# 05_-_RF_READER.net
KiCad netlist of a schematic drawn in Altium Designer
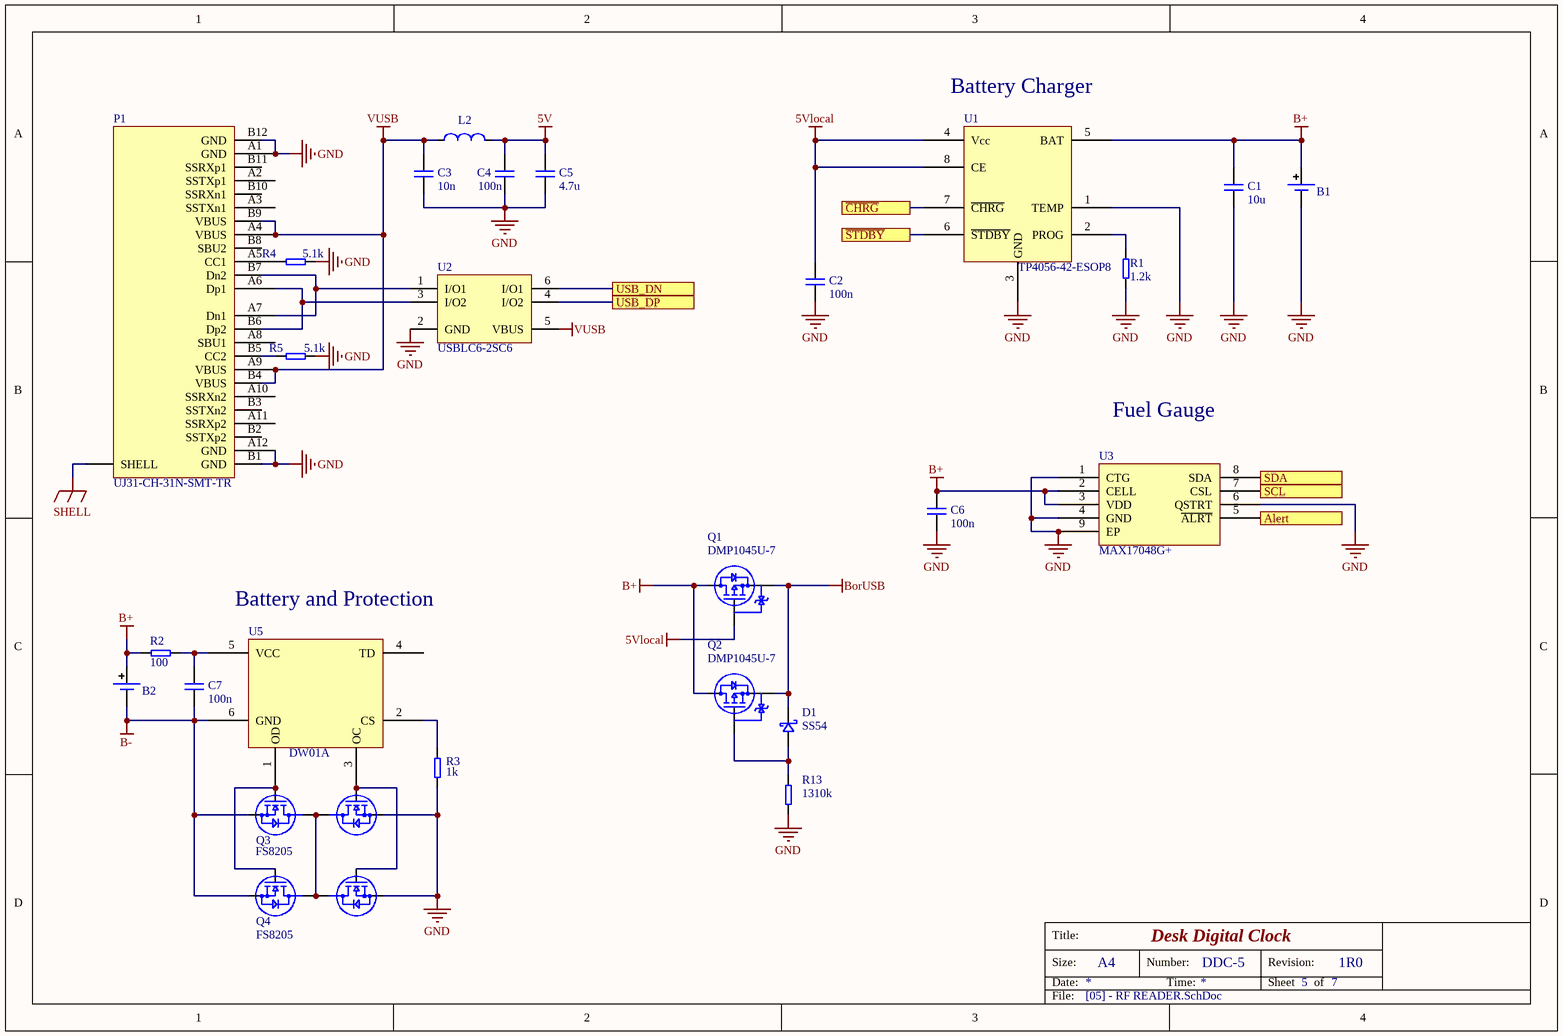
[diagram p0: [05] - RF READER.SchDoc]

(export (version "E")
  (design (tool "Eeschema 10.0.6"))
  (components
    (comp (ref "B1") (value "~") (description "BATTERY") (libsource (lib "1") (part "Bat")))
    (comp (ref "B2") (value "~") (description "BATTERY") (libsource (lib "1") (part "Bat")))
    (comp (ref "C1")
      (value "10u")
      (footprint "C0603")
      (description "CAPACITOR")
      (libsource (lib "1") (part "Cap"))
    )
    (comp (ref "C2")
      (value "100n")
      (footprint "C0603")
      (description "CAPACITOR")
      (libsource (lib "1") (part "Cap"))
    )
    (comp (ref "C3")
      (value "10n")
      (footprint "C0603")
      (description "CAPACITOR")
      (libsource (lib "1") (part "Cap"))
    )
    (comp (ref "C4")
      (value "100n")
      (footprint "C0603")
      (description "CAPACITOR")
      (libsource (lib "1") (part "Cap"))
    )
    (comp (ref "C5")
      (value "4.7u")
      (footprint "C0603")
      (description "CAPACITOR")
      (libsource (lib "1") (part "Cap"))
    )
    (comp (ref "C6")
      (value "100n")
      (footprint "C0603")
      (description "CAPACITOR")
      (libsource (lib "1") (part "Cap"))
    )
    (comp (ref "C7")
      (value "100n")
      (footprint "C0603")
      (description "CAPACITOR")
      (libsource (lib "1") (part "Cap"))
    )
    (comp (ref "D1")
      (value "~")
      (footprint "DIOM6959X26N-SS54")
      (description "Diode Shottky")
      (fields (field (name "P/N") "SS54"))
      (libsource (lib "1") (part "Diode_Shottky"))
    )
    (comp (ref "L2")
      (value "~")
      (footprint "C0805")
      (description "Ferrite Bead")
      (libsource (lib "1") (part "Ind"))
    )
    (comp (ref "P1")
      (value "UJ31-CH-31N-SMT-TR")
      (footprint "UJ31-CH-31N-SMT-TR")
      (description "CONN RCPT USB3.1 TYPEC 24POS R/A")
      (fields (field (name "MANUFACTURER") "CUI Devices"))
      (libsource (lib "1") (part "UJ31-CH-31N-SMT-TR"))
    )
    (comp (ref "Q1")
      (value "DMP1045U-7")
      (footprint "SOT23127P600-8N")
      (description "P-CHANNEL ENHANCEMENT MODE MOSFET")
      (fields (field (name "MANUFACTURER") "Diodes Incorporated"))
      (libsource (lib "1") (part "DMP1045U-7"))
    )
    (comp (ref "Q2")
      (value "DMP1045U-7")
      (footprint "SOT23127P600-8N")
      (description "P-CHANNEL ENHANCEMENT MODE MOSFET")
      (fields (field (name "MANUFACTURER") "Diodes Incorporated"))
      (libsource (lib "1") (part "DMP1045U-7"))
    )
    (comp (ref "Q3")
      (value "FS8205")
      (footprint "SOT23-6-MT3420C")
      (description "Dual n-Channel Enhancement Mode power MOSFET")
      (fields (field (name "MANUFACTURER") "Fortune"))
      (libsource (lib "1") (part "FS8205"))
    )
    (comp (ref "Q4")
      (value "FS8205")
      (footprint "SOT23-6-MT3420C")
      (description "Dual n-Channel Enhancement Mode power MOSFET")
      (fields (field (name "MANUFACTURER") "Fortune"))
      (libsource (lib "1") (part "FS8205"))
    )
    (comp (ref "R1")
      (value "1.2k")
      (footprint "R0603")
      (description "RESISTOR")
      (libsource (lib "1") (part "Res"))
    )
    (comp (ref "R2")
      (value "100")
      (footprint "R0603")
      (description "RESISTOR")
      (libsource (lib "1") (part "Res"))
    )
    (comp (ref "R3")
      (value "1k")
      (footprint "R0603")
      (description "RESISTOR")
      (libsource (lib "1") (part "Res"))
    )
    (comp (ref "R4")
      (value "5.1k")
      (footprint "R0603")
      (description "RESISTOR")
      (libsource (lib "1") (part "Res"))
    )
    (comp (ref "R5")
      (value "5.1k")
      (footprint "R0603")
      (description "RESISTOR")
      (libsource (lib "1") (part "Res"))
    )
    (comp (ref "R13")
      (value "1310k")
      (footprint "R0603")
      (description "RESISTOR")
      (libsource (lib "1") (part "Res"))
    )
    (comp (ref "U1")
      (value "TP4056-42-ESOP8")
      (footprint "TP4056-SOIC8-TP")
      (description "1A Standalone Linear Li-lon Battery Charger with Thermal\r\nRegulation in SOP-8")
      (fields (field (name "MANUFACTURER") "TopPower"))
      (libsource (lib "1") (part "TP4056-42-ESOP8"))
    )
    (comp (ref "U2")
      (value "USBLC6-2SC6")
      (footprint "SOT23-6L-USBLC6-2SC6")
      (description "TVS DIODE 5.25V 17V SOT23-6")
      (fields (field (name "MANUFACTURER") "STMicroelectronics"))
      (libsource (lib "1") (part "USBLC6-2SC6"))
    )
    (comp (ref "U3")
      (value "MAX17048G+")
      (footprint "8 TDFN-EP-MAX17048G+")
      (description "Micropower 1 Cell Li+ ModelFuel Gauge")
      (fields (field (name "MANUFACTURER") "Maxim Integrated"))
      (libsource (lib "1") (part "MAX17048G+"))
    )
    (comp (ref "U5")
      (value "DW01A")
      (footprint "SOT23-6-MT3420C")
      (description "2A 2.3-6V Input 1.5MHz Synchronous Step-Down Converter")
      (fields (field (name "MANUFACTURER") "HMsemi"))
      (libsource (lib "1") (part "DW01A"))
    )
  )
  (nets
    (net (code "1") (name "/Alert") (class "Default")
      (node (ref "U3") (pin "5") (pinfunction "~{ALRT}_5") (pintype "passive"))
    )
    (net (code "2") (name "/SCL") (class "Default")
      (node (ref "U3") (pin "7") (pinfunction "CSL_7") (pintype "passive"))
    )
    (net (code "3") (name "/SDA") (class "Default")
      (node (ref "U3") (pin "8") (pinfunction "SDA_8") (pintype "passive"))
    )
    (net (code "4") (name "/USB_DN") (class "Default")
      (node (ref "U2") (pin "6") (pinfunction "I/O1_6") (pintype "passive"))
    )
    (net (code "5") (name "/USB_DP") (class "Default")
      (node (ref "U2") (pin "4") (pinfunction "I/O2_4") (pintype "passive"))
    )
    (net (code "6") (name "/~{CHRG}") (class "Default")
      (node (ref "U1") (pin "7") (pinfunction "~{CHRG}_7") (pintype "passive"))
    )
    (net (code "7") (name "/~{STDBY}") (class "Default")
      (node (ref "U1") (pin "6") (pinfunction "~{STDBY}_6") (pintype "passive"))
    )
    (net (code "8") (name "5V") (class "Default")
      (node (ref "C4") (pin "2") (pinfunction "2_2") (pintype "passive"))
      (node (ref "C5") (pin "2") (pinfunction "2_2") (pintype "passive"))
      (node (ref "L2") (pin "2") (pinfunction "2_2") (pintype "passive"))
    )
    (net (code "9") (name "5Vlocal") (class "Default")
      (node (ref "C2") (pin "2") (pinfunction "2_2") (pintype "passive"))
      (node (ref "Q1") (pin "G") (pinfunction "G_G") (pintype "passive"))
      (node (ref "U1") (pin "4") (pinfunction "Vcc_4") (pintype "passive"))
      (node (ref "U1") (pin "8") (pinfunction "CE_8") (pintype "passive"))
    )
    (net (code "10") (name "B+") (class "Default")
      (node (ref "B1") (pin "2") (pinfunction "2_2") (pintype "passive"))
      (node (ref "B2") (pin "2") (pinfunction "2_2") (pintype "passive"))
      (node (ref "C1") (pin "2") (pinfunction "2_2") (pintype "passive"))
      (node (ref "C6") (pin "2") (pinfunction "2_2") (pintype "passive"))
      (node (ref "Q1") (pin "D") (pinfunction "D_D") (pintype "passive"))
      (node (ref "Q2") (pin "D") (pinfunction "D_D") (pintype "passive"))
      (node (ref "R2") (pin "2") (pinfunction "2_2") (pintype "passive"))
      (node (ref "U1") (pin "5") (pinfunction "BAT_5") (pintype "passive"))
      (node (ref "U3") (pin "2") (pinfunction "CELL_2") (pintype "passive"))
      (node (ref "U3") (pin "3") (pinfunction "VDD_3") (pintype "passive"))
    )
    (net (code "11") (name "B-") (class "Default")
      (node (ref "B2") (pin "1") (pinfunction "1_1") (pintype "passive"))
      (node (ref "C7") (pin "1") (pinfunction "1_1") (pintype "passive"))
      (node (ref "Q3") (pin "1") (pinfunction "S1_1") (pintype "passive"))
      (node (ref "Q4") (pin "1") (pinfunction "S1_1") (pintype "passive"))
      (node (ref "U5") (pin "6") (pinfunction "GND_6") (pintype "passive"))
    )
    (net (code "12") (name "BorUSB") (class "Default")
      (node (ref "D1") (pin "1") (pinfunction "1_1") (pintype "passive"))
      (node (ref "Q1") (pin "S") (pinfunction "S_S") (pintype "passive"))
      (node (ref "Q2") (pin "S") (pinfunction "S_S") (pintype "passive"))
    )
    (net (code "13") (name "GND") (class "Default")
      (node (ref "B1") (pin "1") (pinfunction "1_1") (pintype "passive"))
      (node (ref "C1") (pin "1") (pinfunction "1_1") (pintype "passive"))
      (node (ref "C2") (pin "1") (pinfunction "1_1") (pintype "passive"))
      (node (ref "C3") (pin "1") (pinfunction "1_1") (pintype "passive"))
      (node (ref "C4") (pin "1") (pinfunction "1_1") (pintype "passive"))
      (node (ref "C5") (pin "1") (pinfunction "1_1") (pintype "passive"))
      (node (ref "C6") (pin "1") (pinfunction "1_1") (pintype "passive"))
      (node (ref "P1") (pin "A1") (pinfunction "GND_A1") (pintype "passive"))
      (node (ref "P1") (pin "A12") (pinfunction "GND_A12") (pintype "passive"))
      (node (ref "P1") (pin "B1") (pinfunction "GND_B1") (pintype "passive"))
      (node (ref "P1") (pin "B12") (pinfunction "GND_B12") (pintype "passive"))
      (node (ref "Q3") (pin "3") (pinfunction "S2_3") (pintype "passive"))
      (node (ref "Q4") (pin "3") (pinfunction "S2_3") (pintype "passive"))
      (node (ref "R1") (pin "1") (pinfunction "1_1") (pintype "passive"))
      (node (ref "R13") (pin "1") (pinfunction "1_1") (pintype "passive"))
      (node (ref "R3") (pin "1") (pinfunction "1_1") (pintype "passive"))
      (node (ref "R4") (pin "1") (pinfunction "1_1") (pintype "passive"))
      (node (ref "R5") (pin "1") (pinfunction "1_1") (pintype "passive"))
      (node (ref "U1") (pin "1") (pinfunction "TEMP_1") (pintype "passive"))
      (node (ref "U1") (pin "3") (pinfunction "GND_3") (pintype "passive"))
      (node (ref "U2") (pin "2") (pinfunction "GND_2") (pintype "passive"))
      (node (ref "U3") (pin "1") (pinfunction "CTG_1") (pintype "passive"))
      (node (ref "U3") (pin "4") (pinfunction "GND_4") (pintype "passive"))
      (node (ref "U3") (pin "6") (pinfunction "QSTRT_6") (pintype "passive"))
      (node (ref "U3") (pin "9") (pinfunction "EP_9") (pintype "passive"))
    )
    (net (code "14") (name "Net-(D1-Pad2)") (class "Default")
      (node (ref "D1") (pin "2") (pinfunction "2_2") (pintype "passive"))
      (node (ref "Q2") (pin "G") (pinfunction "G_G") (pintype "passive"))
      (node (ref "R13") (pin "2") (pinfunction "2_2") (pintype "passive"))
    )
    (net (code "15") (name "Net-(P1-CC1)") (class "Default")
      (node (ref "P1") (pin "A5") (pinfunction "CC1_A5") (pintype "passive"))
      (node (ref "R4") (pin "2") (pinfunction "2_2") (pintype "passive"))
    )
    (net (code "16") (name "Net-(P1-CC2)") (class "Default")
      (node (ref "P1") (pin "B5") (pinfunction "CC2_B5") (pintype "passive"))
      (node (ref "R5") (pin "2") (pinfunction "2_2") (pintype "passive"))
    )
    (net (code "17") (name "Net-(P1-Dn1)") (class "Default")
      (node (ref "P1") (pin "A7") (pinfunction "Dn1_A7") (pintype "passive"))
      (node (ref "P1") (pin "B7") (pinfunction "Dn2_B7") (pintype "passive"))
      (node (ref "U2") (pin "1") (pinfunction "I/O1_1") (pintype "passive"))
    )
    (net (code "18") (name "Net-(P1-Dp1)") (class "Default")
      (node (ref "P1") (pin "A6") (pinfunction "Dp1_A6") (pintype "passive"))
      (node (ref "P1") (pin "B6") (pinfunction "Dp2_B6") (pintype "passive"))
      (node (ref "U2") (pin "3") (pinfunction "I/O2_3") (pintype "passive"))
    )
    (net (code "19") (name "Net-(Q3-D12-Pad2)") (class "Default")
      (node (ref "Q3") (pin "2") (pinfunction "D12_2") (pintype "passive"))
      (node (ref "Q3") (pin "5") (pinfunction "D12_5") (pintype "passive"))
      (node (ref "Q4") (pin "2") (pinfunction "D12_2") (pintype "passive"))
      (node (ref "Q4") (pin "5") (pinfunction "D12_5") (pintype "passive"))
    )
    (net (code "20") (name "Net-(Q3-G1)") (class "Default")
      (node (ref "Q3") (pin "6") (pinfunction "G1_6") (pintype "passive"))
      (node (ref "Q4") (pin "6") (pinfunction "G1_6") (pintype "passive"))
      (node (ref "U5") (pin "1") (pinfunction "OD_1") (pintype "passive"))
    )
    (net (code "21") (name "Net-(Q3-G2)") (class "Default")
      (node (ref "Q3") (pin "4") (pinfunction "G2_4") (pintype "passive"))
      (node (ref "Q4") (pin "4") (pinfunction "G2_4") (pintype "passive"))
      (node (ref "U5") (pin "3") (pinfunction "OC_3") (pintype "passive"))
    )
    (net (code "22") (name "Net-(U1-PROG)") (class "Default")
      (node (ref "R1") (pin "2") (pinfunction "2_2") (pintype "passive"))
      (node (ref "U1") (pin "2") (pinfunction "PROG_2") (pintype "passive"))
    )
    (net (code "23") (name "Net-(U5-CS)") (class "Default")
      (node (ref "R3") (pin "2") (pinfunction "2_2") (pintype "passive"))
      (node (ref "U5") (pin "2") (pinfunction "CS_2") (pintype "passive"))
    )
    (net (code "24") (name "Net-(U5-VCC)") (class "Default")
      (node (ref "C7") (pin "2") (pinfunction "2_2") (pintype "passive"))
      (node (ref "R2") (pin "1") (pinfunction "1_1") (pintype "passive"))
      (node (ref "U5") (pin "5") (pinfunction "VCC_5") (pintype "passive"))
    )
    (net (code "25") (name "SHELL") (class "Default")
      (node (ref "P1") (pin "0") (pinfunction "SHELL_0") (pintype "passive"))
    )
    (net (code "26") (name "VUSB") (class "Default")
      (node (ref "C3") (pin "2") (pinfunction "2_2") (pintype "passive"))
      (node (ref "L2") (pin "1") (pinfunction "1_1") (pintype "passive"))
      (node (ref "P1") (pin "A4") (pinfunction "VBUS_A4") (pintype "passive"))
      (node (ref "P1") (pin "A9") (pinfunction "VBUS_A9") (pintype "passive"))
      (node (ref "P1") (pin "B4") (pinfunction "VBUS_B4") (pintype "passive"))
      (node (ref "P1") (pin "B9") (pinfunction "VBUS_B9") (pintype "passive"))
      (node (ref "U2") (pin "5") (pinfunction "VBUS_5") (pintype "passive"))
    )
    (net (code "27") (name "unconnected-(P1-SBU1-PadA8)") (class "Default")
      (node (ref "P1") (pin "A8") (pinfunction "SBU1_A8") (pintype "passive"))
    )
    (net (code "28") (name "unconnected-(P1-SBU2-PadB8)") (class "Default")
      (node (ref "P1") (pin "B8") (pinfunction "SBU2_B8") (pintype "passive"))
    )
    (net (code "29") (name "unconnected-(P1-SSRXn1-PadB10)") (class "Default")
      (node (ref "P1") (pin "B10") (pinfunction "SSRXn1_B10") (pintype "passive"))
    )
    (net (code "30") (name "unconnected-(P1-SSRXn2-PadA10)") (class "Default")
      (node (ref "P1") (pin "A10") (pinfunction "SSRXn2_A10") (pintype "passive"))
    )
    (net (code "31") (name "unconnected-(P1-SSRXp1-PadB11)") (class "Default")
      (node (ref "P1") (pin "B11") (pinfunction "SSRXp1_B11") (pintype "passive"))
    )
    (net (code "32") (name "unconnected-(P1-SSRXp2-PadA11)") (class "Default")
      (node (ref "P1") (pin "A11") (pinfunction "SSRXp2_A11") (pintype "passive"))
    )
    (net (code "33") (name "unconnected-(P1-SSTXn1-PadA3)") (class "Default")
      (node (ref "P1") (pin "A3") (pinfunction "SSTXn1_A3") (pintype "passive"))
    )
    (net (code "34") (name "unconnected-(P1-SSTXn2-PadB3)") (class "Default")
      (node (ref "P1") (pin "B3") (pinfunction "SSTXn2_B3") (pintype "passive"))
    )
    (net (code "35") (name "unconnected-(P1-SSTXp1-PadA2)") (class "Default")
      (node (ref "P1") (pin "A2") (pinfunction "SSTXp1_A2") (pintype "passive"))
    )
    (net (code "36") (name "unconnected-(P1-SSTXp2-PadB2)") (class "Default")
      (node (ref "P1") (pin "B2") (pinfunction "SSTXp2_B2") (pintype "passive"))
    )
    (net (code "37") (name "unconnected-(U5-TD-Pad4)") (class "Default")
      (node (ref "U5") (pin "4") (pinfunction "TD_4") (pintype "passive"))
    )
  )
)
